# FLEXQCM_V1_2.net
KiCad netlist of a schematic drawn in EAGLE
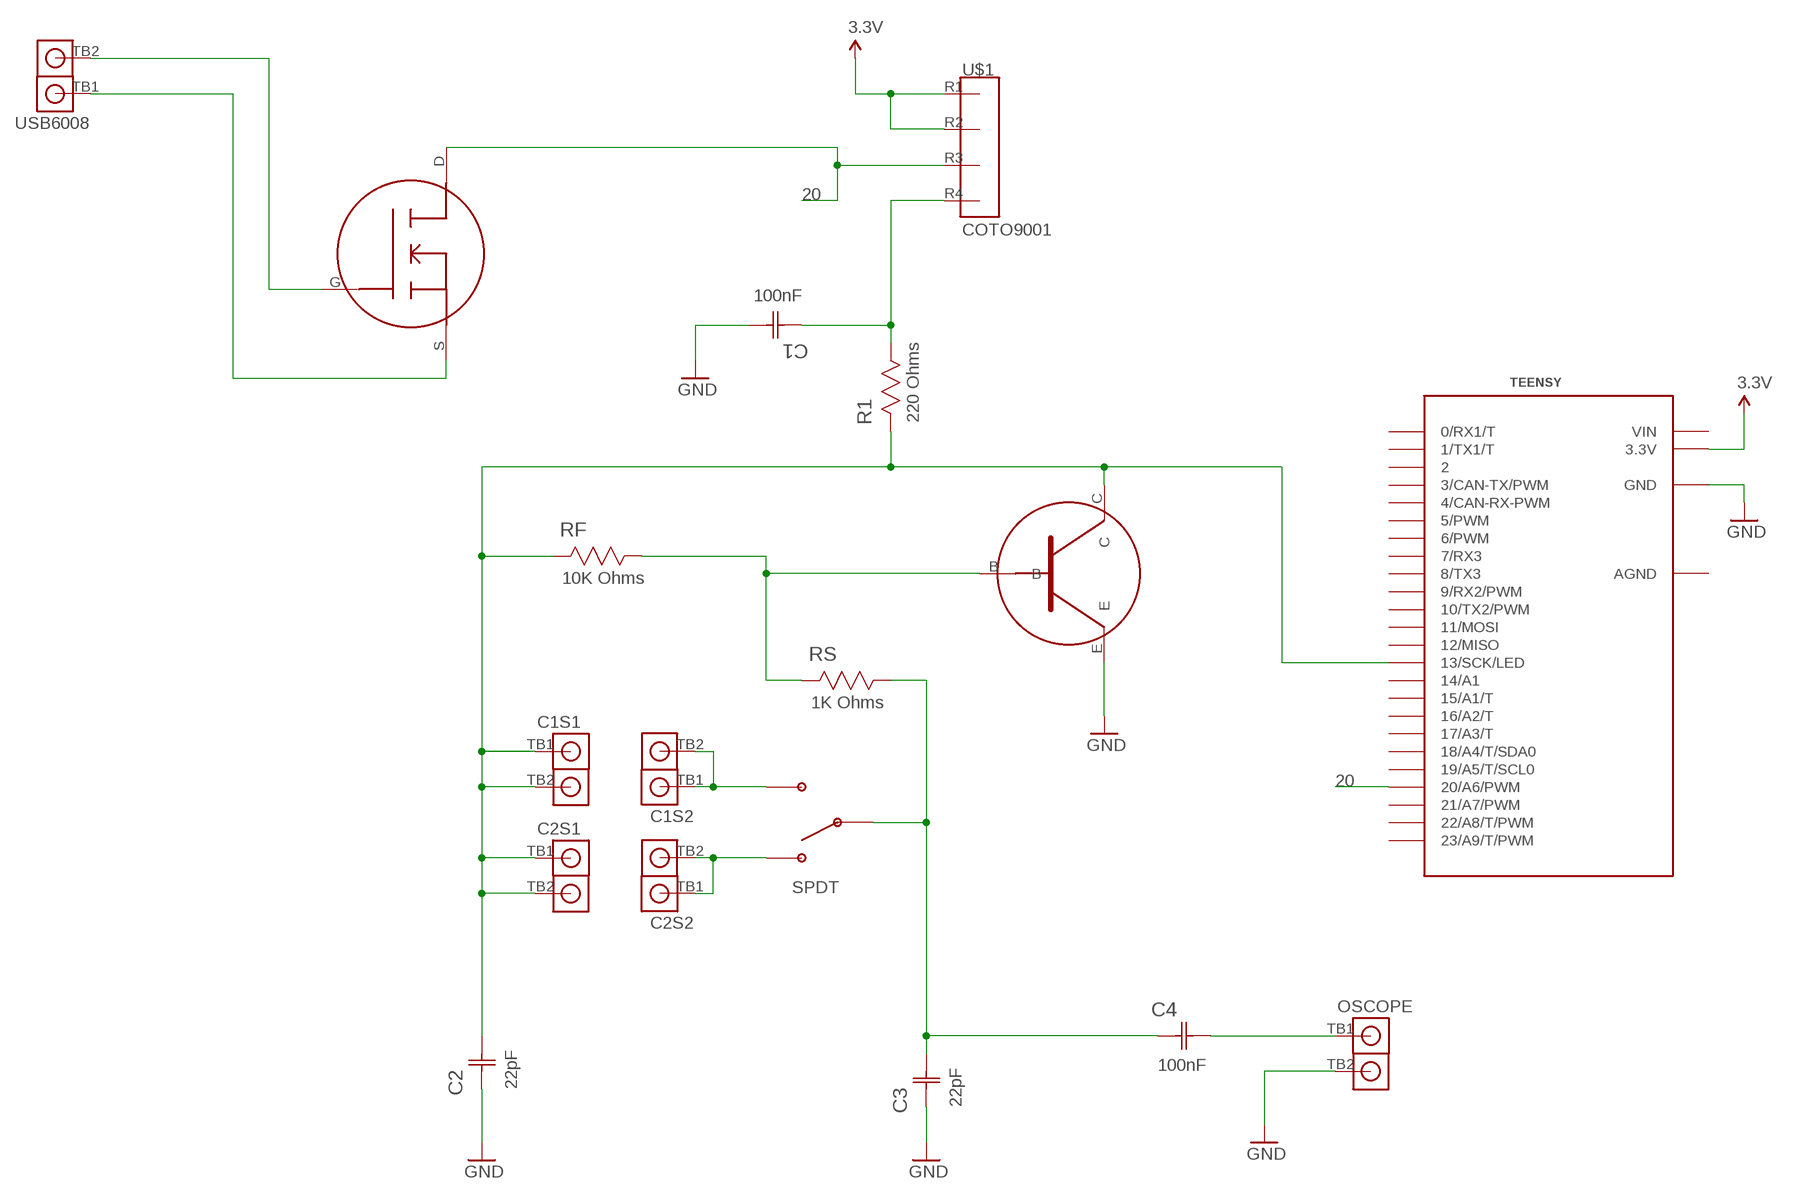
[diagram p0: schematic, sheet 1]

(export (version "E")
  (design (tool "Eeschema 10.0.6"))
  (components
    (comp (ref "C1")
      (value "100nF")
      (footprint "eagle-import:CAPC3216X88N")
      (fields (field (name "MPN") "C1206C104K1RACTU") (field (name "TOLERANCE") "±10%"))
      (libsource (lib "eagle-import") (part "C1206C104K1RACTU"))
    )
    (comp (ref "C1S1")
      (value "TERMBLOCKX2")
      (footprint "eagle-import:TERMBLOCKX2")
      (libsource (lib "eagle-import") (part "TERMBLOCKX2"))
    )
    (comp (ref "C1S2")
      (value "TERMBLOCKX2")
      (footprint "eagle-import:TERMBLOCKX2")
      (libsource (lib "eagle-import") (part "TERMBLOCKX2"))
    )
    (comp (ref "C2")
      (value "22pF")
      (footprint "eagle-import:CAPC3216X88N")
      (fields (field (name "MPN") "C1206C220J5GACTU") (field (name "TOLERANCE") "±5%"))
      (libsource (lib "eagle-import") (part "C1206C220J5GACTU"))
    )
    (comp (ref "C2S1")
      (value "TERMBLOCKX2")
      (footprint "eagle-import:TERMBLOCKX2")
      (libsource (lib "eagle-import") (part "TERMBLOCKX2"))
    )
    (comp (ref "C2S2")
      (value "TERMBLOCKX2")
      (footprint "eagle-import:TERMBLOCKX2")
      (libsource (lib "eagle-import") (part "TERMBLOCKX2"))
    )
    (comp (ref "C3")
      (value "22pF")
      (footprint "eagle-import:CAPC3216X88N")
      (fields (field (name "MPN") "C1206C220J5GACTU") (field (name "TOLERANCE") "±5%"))
      (libsource (lib "eagle-import") (part "C1206C220J5GACTU"))
    )
    (comp (ref "C4")
      (value "100nF")
      (footprint "eagle-import:CAPC3216X88N")
      (fields (field (name "MPN") "C1206C104K1RACTU") (field (name "TOLERANCE") "±10%"))
      (libsource (lib "eagle-import") (part "C1206C104K1RACTU"))
    )
    (comp (ref "OSCOPE")
      (value "TERMBLOCKX2")
      (footprint "eagle-import:TERMBLOCKX2")
      (libsource (lib "eagle-import") (part "TERMBLOCKX2"))
    )
    (comp (ref "R1")
      (value "220 Ohms")
      (footprint "eagle-import:RESC3216X71N")
      (fields (field (name "MPN") "CRCW1206220RJNEA") (field (name "TOLERANCE") "±5%"))
      (libsource (lib "eagle-import") (part "CRCW1206220RJNEA"))
    )
    (comp (ref "RF")
      (value "10K Ohms")
      (footprint "eagle-import:RESC3216X71N")
      (fields (field (name "MPN") "CRCW120610K0FKEA") (field (name "TOLERANCE") "±1%"))
      (libsource (lib "eagle-import") (part "CRCW120610K0FKEA"))
    )
    (comp (ref "RS")
      (value "1K Ohms")
      (footprint "eagle-import:RESC3216X71N")
      (fields (field (name "MPN") "CRCW12061K00FKEA") (field (name "TOLERANCE") "±1%"))
      (libsource (lib "eagle-import") (part "CRCW12061K00FKEA"))
    )
    (comp (ref "SPDT")
      (value "SPDTSWITCH")
      (footprint "eagle-import:SPDTSWITCH")
      (libsource (lib "eagle-import") (part "SPDTSWITCH"))
    )
    (comp (ref "TEENSY")
      (value "TEENSY_3.1_DIL")
      (footprint "eagle-import:TEENSY3-DIL")
      (libsource (lib "eagle-import") (part "TEENSY_3.1_DIL"))
    )
    (comp (ref "U$1")
      (value "COTO9001")
      (footprint "eagle-import:COTO9001")
      (libsource (lib "eagle-import") (part "COTO9001"))
    )
    (comp (ref "U1")
      (value "2N7002BK")
      (footprint "eagle-import:SOT95P230X110-3N")
      (libsource (lib "eagle-import") (part "2N7002BK"))
    )
    (comp (ref "U2")
      (value "BC847C-7-F")
      (footprint "eagle-import:SOT103P240X110-3N")
      (libsource (lib "eagle-import") (part "BC847C-7-F"))
    )
    (comp (ref "USB6008")
      (value "TERMBLOCKX2")
      (footprint "eagle-import:TERMBLOCKX2")
      (libsource (lib "eagle-import") (part "TERMBLOCKX2"))
    )
  )
  (nets
    (net (code "1") (name "/20") (class "Default")
      (node (ref "TEENSY") (pin "20/A6") (pinfunction "20/A6/PWM_20/A6") (pintype "bidirectional"))
      (node (ref "U$1") (pin "R3") (pinfunction "R3_R3") (pintype "bidirectional"))
      (node (ref "U1") (pin "D") (pinfunction "D_D") (pintype "bidirectional"))
    )
    (net (code "2") (name "/AGND") (class "Default")
      (node (ref "TEENSY") (pin "AGND") (pinfunction "AGND_AGND") (pintype "power_in"))
    )
    (net (code "3") (name "/VIN") (class "Default")
      (node (ref "TEENSY") (pin "VIN") (pinfunction "VIN_VIN") (pintype "power_in"))
    )
    (net (code "4") (name "3.3V") (class "Default")
      (node (ref "TEENSY") (pin "3.3V") (pinfunction "3.3V_3.3V") (pintype "power_in"))
      (node (ref "U$1") (pin "R1") (pinfunction "R1_R1") (pintype "bidirectional"))
      (node (ref "U$1") (pin "R2") (pinfunction "R2_R2") (pintype "bidirectional"))
    )
    (net (code "5") (name "GND") (class "Default")
      (node (ref "C1") (pin "2") (pinfunction "C2_2") (pintype "passive"))
      (node (ref "C2") (pin "1") (pinfunction "C1_1") (pintype "passive"))
      (node (ref "C3") (pin "1") (pinfunction "C1_1") (pintype "passive"))
      (node (ref "OSCOPE") (pin "TB2") (pinfunction "TB2_TB2") (pintype "bidirectional"))
      (node (ref "TEENSY") (pin "GND") (pinfunction "GND_GND") (pintype "power_in"))
      (node (ref "U2") (pin "E") (pinfunction "E_E") (pintype "bidirectional"))
    )
    (net (code "6") (name "Net-(C1-C1)") (class "Default")
      (node (ref "C1") (pin "1") (pinfunction "C1_1") (pintype "passive"))
      (node (ref "R1") (pin "1") (pinfunction "1_1") (pintype "passive"))
      (node (ref "U$1") (pin "R4") (pinfunction "R4_R4") (pintype "bidirectional"))
    )
    (net (code "7") (name "Net-(C1S2-PadTB1)") (class "Default")
      (node (ref "C1S2") (pin "TB1") (pinfunction "TB1_TB1") (pintype "bidirectional"))
      (node (ref "C1S2") (pin "TB2") (pinfunction "TB2_TB2") (pintype "bidirectional"))
      (node (ref "SPDT") (pin "SW3") (pinfunction "SW3_SW3") (pintype "bidirectional"))
    )
    (net (code "8") (name "Net-(C2-C2)") (class "Default")
      (node (ref "C1S1") (pin "TB1") (pinfunction "TB1_TB1") (pintype "bidirectional"))
      (node (ref "C1S1") (pin "TB2") (pinfunction "TB2_TB2") (pintype "bidirectional"))
      (node (ref "C2") (pin "2") (pinfunction "C2_2") (pintype "passive"))
      (node (ref "C2S1") (pin "TB1") (pinfunction "TB1_TB1") (pintype "bidirectional"))
      (node (ref "C2S1") (pin "TB2") (pinfunction "TB2_TB2") (pintype "bidirectional"))
      (node (ref "R1") (pin "2") (pinfunction "2_2") (pintype "passive"))
      (node (ref "RF") (pin "2") (pinfunction "2_2") (pintype "passive"))
      (node (ref "TEENSY") (pin "13") (pinfunction "13/SCK/LED_13") (pintype "bidirectional"))
      (node (ref "U2") (pin "C") (pinfunction "C_C") (pintype "bidirectional"))
    )
    (net (code "9") (name "Net-(C2S2-PadTB1)") (class "Default")
      (node (ref "C2S2") (pin "TB1") (pinfunction "TB1_TB1") (pintype "bidirectional"))
      (node (ref "C2S2") (pin "TB2") (pinfunction "TB2_TB2") (pintype "bidirectional"))
      (node (ref "SPDT") (pin "SW1") (pinfunction "SW1_SW1") (pintype "bidirectional"))
    )
    (net (code "10") (name "Net-(C3-C2)") (class "Default")
      (node (ref "C3") (pin "2") (pinfunction "C2_2") (pintype "passive"))
      (node (ref "C4") (pin "1") (pinfunction "C1_1") (pintype "passive"))
      (node (ref "RS") (pin "1") (pinfunction "1_1") (pintype "passive"))
      (node (ref "SPDT") (pin "SW2") (pinfunction "SW2_SW2") (pintype "bidirectional"))
    )
    (net (code "11") (name "Net-(C4-C2)") (class "Default")
      (node (ref "C4") (pin "2") (pinfunction "C2_2") (pintype "passive"))
      (node (ref "OSCOPE") (pin "TB1") (pinfunction "TB1_TB1") (pintype "bidirectional"))
    )
    (net (code "12") (name "Net-(RF-Pad1)") (class "Default")
      (node (ref "RF") (pin "1") (pinfunction "1_1") (pintype "passive"))
      (node (ref "RS") (pin "2") (pinfunction "2_2") (pintype "passive"))
      (node (ref "U2") (pin "B") (pinfunction "B_B") (pintype "bidirectional"))
    )
    (net (code "13") (name "Net-(U1-PadG)") (class "Default")
      (node (ref "U1") (pin "G") (pinfunction "G_G") (pintype "bidirectional"))
      (node (ref "USB6008") (pin "TB2") (pinfunction "TB2_TB2") (pintype "bidirectional"))
    )
    (net (code "14") (name "Net-(U1-PadS)") (class "Default")
      (node (ref "U1") (pin "S") (pinfunction "S_S") (pintype "bidirectional"))
      (node (ref "USB6008") (pin "TB1") (pinfunction "TB1_TB1") (pintype "bidirectional"))
    )
    (net (code "15") (name "unconnected-(TEENSY-0{slash}RX1{slash}T-Pad0)") (class "Default")
      (node (ref "TEENSY") (pin "0") (pinfunction "0/RX1/T_0") (pintype "bidirectional"))
    )
    (net (code "16") (name "unconnected-(TEENSY-1{slash}TX1{slash}T-Pad1)") (class "Default")
      (node (ref "TEENSY") (pin "1") (pinfunction "1/TX1/T_1") (pintype "bidirectional"))
    )
    (net (code "17") (name "unconnected-(TEENSY-3{slash}CAN-TX{slash}PWM-Pad3)") (class "Default")
      (node (ref "TEENSY") (pin "3") (pinfunction "3/CAN-TX/PWM_3") (pintype "bidirectional"))
    )
    (net (code "18") (name "unconnected-(TEENSY-4{slash}CAN-RX-PWM-Pad4)") (class "Default")
      (node (ref "TEENSY") (pin "4") (pinfunction "4/CAN-RX-PWM_4") (pintype "bidirectional"))
    )
    (net (code "19") (name "unconnected-(TEENSY-5{slash}PWM-Pad5)") (class "Default")
      (node (ref "TEENSY") (pin "5") (pinfunction "5/PWM_5") (pintype "bidirectional"))
    )
    (net (code "20") (name "unconnected-(TEENSY-6{slash}PWM-Pad6)") (class "Default")
      (node (ref "TEENSY") (pin "6") (pinfunction "6/PWM_6") (pintype "bidirectional"))
    )
    (net (code "21") (name "unconnected-(TEENSY-7{slash}RX3-Pad7)") (class "Default")
      (node (ref "TEENSY") (pin "7") (pinfunction "7/RX3_7") (pintype "bidirectional"))
    )
    (net (code "22") (name "unconnected-(TEENSY-8{slash}TX3-Pad8)") (class "Default")
      (node (ref "TEENSY") (pin "8") (pinfunction "8/TX3_8") (pintype "bidirectional"))
    )
    (net (code "23") (name "unconnected-(TEENSY-9{slash}RX2{slash}PWM-Pad9)") (class "Default")
      (node (ref "TEENSY") (pin "9") (pinfunction "9/RX2/PWM_9") (pintype "bidirectional"))
    )
    (net (code "24") (name "unconnected-(TEENSY-10{slash}TX2{slash}PWM-Pad10)") (class "Default")
      (node (ref "TEENSY") (pin "10") (pinfunction "10/TX2/PWM_10") (pintype "bidirectional"))
    )
    (net (code "25") (name "unconnected-(TEENSY-11{slash}MOSI-Pad11)") (class "Default")
      (node (ref "TEENSY") (pin "11") (pinfunction "11/MOSI_11") (pintype "bidirectional"))
    )
    (net (code "26") (name "unconnected-(TEENSY-12{slash}MISO-Pad12)") (class "Default")
      (node (ref "TEENSY") (pin "12") (pinfunction "12/MISO_12") (pintype "bidirectional"))
    )
    (net (code "27") (name "unconnected-(TEENSY-14{slash}A1-Pad14{slash}A0)") (class "Default")
      (node (ref "TEENSY") (pin "14/A0") (pinfunction "14/A1_14/A0") (pintype "bidirectional"))
    )
    (net (code "28") (name "unconnected-(TEENSY-15{slash}A1{slash}T-Pad15{slash}A1)") (class "Default")
      (node (ref "TEENSY") (pin "15/A1") (pinfunction "15/A1/T_15/A1") (pintype "bidirectional"))
    )
    (net (code "29") (name "unconnected-(TEENSY-16{slash}A2{slash}T-Pad16{slash}A2)") (class "Default")
      (node (ref "TEENSY") (pin "16/A2") (pinfunction "16/A2/T_16/A2") (pintype "bidirectional"))
    )
    (net (code "30") (name "unconnected-(TEENSY-17{slash}A3{slash}T-Pad17{slash}A3)") (class "Default")
      (node (ref "TEENSY") (pin "17/A3") (pinfunction "17/A3/T_17/A3") (pintype "bidirectional"))
    )
    (net (code "31") (name "unconnected-(TEENSY-18{slash}A4{slash}T{slash}SDA0-Pad18{slash}A4)") (class "Default")
      (node (ref "TEENSY") (pin "18/A4") (pinfunction "18/A4/T/SDA0_18/A4") (pintype "bidirectional"))
    )
    (net (code "32") (name "unconnected-(TEENSY-19{slash}A5{slash}T{slash}SCL0-Pad19{slash}A5)") (class "Default")
      (node (ref "TEENSY") (pin "19/A5") (pinfunction "19/A5/T/SCL0_19/A5") (pintype "bidirectional"))
    )
    (net (code "33") (name "unconnected-(TEENSY-21{slash}A7{slash}PWM-Pad21{slash}A7)") (class "Default")
      (node (ref "TEENSY") (pin "21/A7") (pinfunction "21/A7/PWM_21/A7") (pintype "bidirectional"))
    )
    (net (code "34") (name "unconnected-(TEENSY-22{slash}A8{slash}T{slash}PWM-Pad22{slash}A8)") (class "Default")
      (node (ref "TEENSY") (pin "22/A8") (pinfunction "22/A8/T/PWM_22/A8") (pintype "bidirectional"))
    )
    (net (code "35") (name "unconnected-(TEENSY-23{slash}A9{slash}T{slash}PWM-Pad23{slash}A9)") (class "Default")
      (node (ref "TEENSY") (pin "23/A9") (pinfunction "23/A9/T/PWM_23/A9") (pintype "bidirectional"))
    )
    (net (code "36") (name "unconnected-(TEENSY-Pad2)") (class "Default")
      (node (ref "TEENSY") (pin "2") (pinfunction "2_2") (pintype "bidirectional"))
    )
  )
)
